# flexPCB_rev.net
KiCad netlist of a schematic drawn in Altium Designer
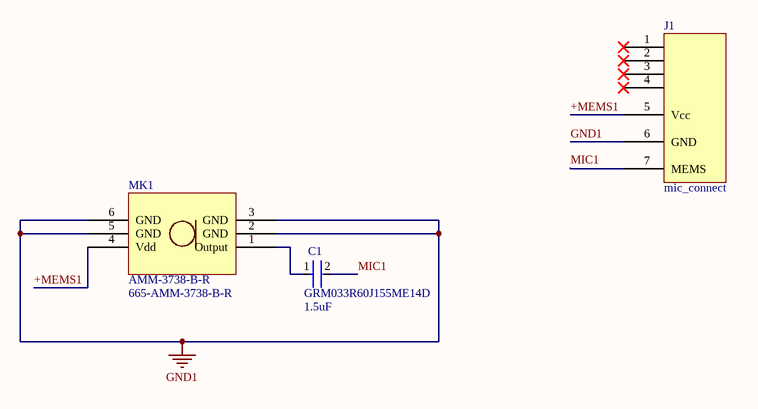
[diagram p0: flexPCB_rev.SchDoc]

(export (version "E")
  (design (tool "Eeschema 10.0.6"))
  (components
    (comp (ref "C1")
      (value "GRM033R60J155ME14D")
      (footprint "FP-GRM033-0_03-IPC_B")
      (description "Chip Multilayer Ceramic Capacitors for General Purpose, 0201, 1.5uF, X5R, 15%, 20%, 6.3V")
      (fields (field (name "TOLERANCE") "20%"))
      (libsource (lib "Altium Content Vault") (part "b4654b650e69147ec39a6b967a45e02"))
    )
    (comp (ref "J1")
      (value "mic_connect")
      (footprint "mic_connect")
      (libsource (lib "Analog_mic_breakout") (part "mic_connect"))
    )
    (comp (ref "MK1")
      (value "AMM-3738-B-R")
      (footprint "665-AMM-3738-B-R")
      (fields
        (field (name "MANUFACTURER") "PUI Audio")
        (field (name "SUPPLIER PART NUMBER 1") "665-AMM-3738-B-R")
      )
      (libsource (lib "Analog_mic_breakout") (part "AMM-3738-B-R"))
    )
  )
  (nets
    (net (code "1") (name "/+MEMS1") (class "Default")
      (node (ref "J1") (pin "5") (pinfunction "Vcc_5") (pintype "passive"))
      (node (ref "MK1") (pin "4") (pinfunction "Vdd_4") (pintype "power_in"))
    )
    (net (code "2") (name "/MIC1") (class "Default")
      (node (ref "C1") (pin "2") (pinfunction "2_2") (pintype "passive"))
      (node (ref "J1") (pin "7") (pinfunction "MEMS_7") (pintype "passive"))
    )
    (net (code "3") (name "GND1") (class "Default")
      (node (ref "J1") (pin "6") (pinfunction "GND_6") (pintype "passive"))
      (node (ref "MK1") (pin "2") (pinfunction "GND_2") (pintype "power_in"))
      (node (ref "MK1") (pin "3") (pinfunction "GND_3") (pintype "power_in"))
      (node (ref "MK1") (pin "5") (pinfunction "GND_5") (pintype "power_in"))
      (node (ref "MK1") (pin "6") (pinfunction "GND_6") (pintype "power_in"))
    )
    (net (code "4") (name "Net-(MK1-Output)") (class "Default")
      (node (ref "C1") (pin "1") (pinfunction "1_1") (pintype "passive"))
      (node (ref "MK1") (pin "1") (pinfunction "Output_1") (pintype "passive"))
    )
    (net (code "5") (name "unconnected-(J1-Pad1)") (class "Default")
      (node (ref "J1") (pin "1") (pintype "passive+no_connect"))
    )
    (net (code "6") (name "unconnected-(J1-Pad2)") (class "Default")
      (node (ref "J1") (pin "2") (pintype "passive+no_connect"))
    )
    (net (code "7") (name "unconnected-(J1-Pad3)") (class "Default")
      (node (ref "J1") (pin "3") (pintype "passive+no_connect"))
    )
    (net (code "8") (name "unconnected-(J1-Pad4)") (class "Default")
      (node (ref "J1") (pin "4") (pintype "passive+no_connect"))
    )
  )
)
